# Debugger.net
KiCad netlist of a schematic drawn in Altium Designer
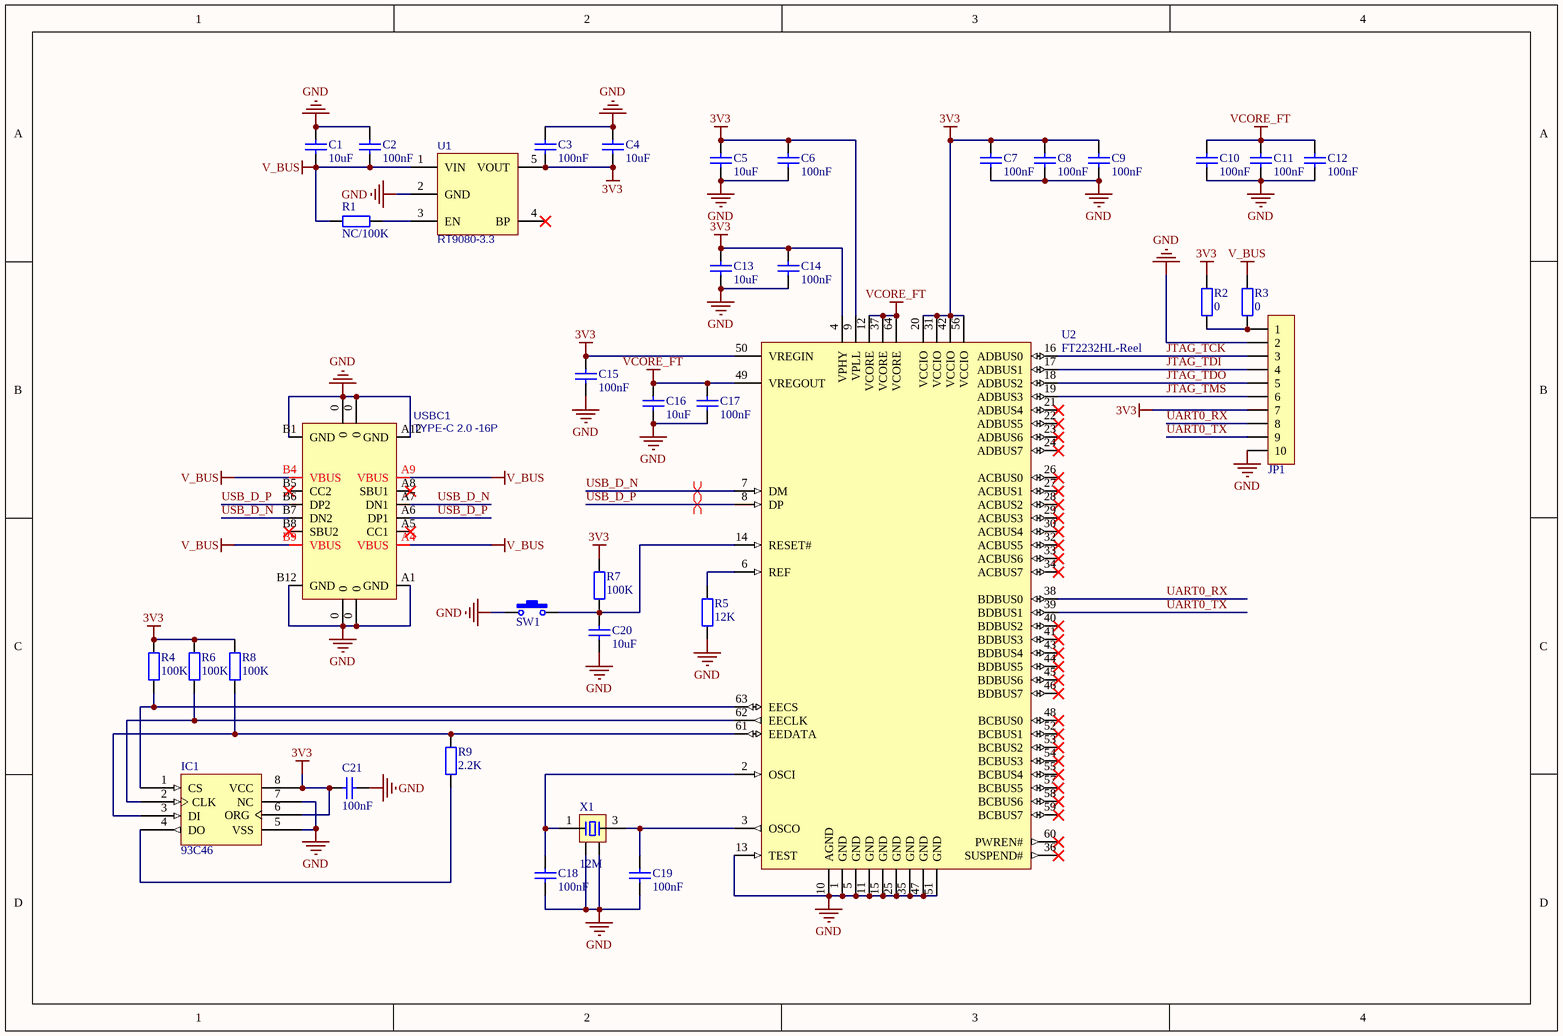
[diagram p0: Debugger.SchDoc]

(export (version "E")
  (design (tool "Eeschema 10.0.6"))
  (components
    (comp (ref "C1")
      (value "10uF")
      (footprint "C0603_L")
      (description "贴片电容/MLCC电容")
      (libsource (lib "0.1 - 电阻-电容-电感-晶振-晶体-磁珠-电位器-法拉电容-馈通电容") (part "C"))
    )
    (comp (ref "C2")
      (value "100nF")
      (footprint "C0603_L")
      (description "贴片电容/MLCC电容")
      (libsource (lib "0.1 - 电阻-电容-电感-晶振-晶体-磁珠-电位器-法拉电容-馈通电容") (part "C"))
    )
    (comp (ref "C3")
      (value "100nF")
      (footprint "C0603_L")
      (description "贴片电容/MLCC电容")
      (libsource (lib "0.1 - 电阻-电容-电感-晶振-晶体-磁珠-电位器-法拉电容-馈通电容") (part "C"))
    )
    (comp (ref "C4")
      (value "10uF")
      (footprint "C0603_L")
      (description "贴片电容/MLCC电容")
      (libsource (lib "0.1 - 电阻-电容-电感-晶振-晶体-磁珠-电位器-法拉电容-馈通电容") (part "C"))
    )
    (comp (ref "C5")
      (value "10uF")
      (footprint "C0603_L")
      (description "贴片电容/MLCC电容")
      (libsource (lib "0.1 - 电阻-电容-电感-晶振-晶体-磁珠-电位器-法拉电容-馈通电容") (part "C"))
    )
    (comp (ref "C6")
      (value "100nF")
      (footprint "C0603_L")
      (description "贴片电容/MLCC电容")
      (libsource (lib "0.1 - 电阻-电容-电感-晶振-晶体-磁珠-电位器-法拉电容-馈通电容") (part "C"))
    )
    (comp (ref "C7")
      (value "100nF")
      (footprint "C0603_L")
      (description "贴片电容/MLCC电容")
      (libsource (lib "0.1 - 电阻-电容-电感-晶振-晶体-磁珠-电位器-法拉电容-馈通电容") (part "C"))
    )
    (comp (ref "C8")
      (value "100nF")
      (footprint "C0603_L")
      (description "贴片电容/MLCC电容")
      (libsource (lib "0.1 - 电阻-电容-电感-晶振-晶体-磁珠-电位器-法拉电容-馈通电容") (part "C"))
    )
    (comp (ref "C9")
      (value "100nF")
      (footprint "C0603_L")
      (description "贴片电容/MLCC电容")
      (libsource (lib "0.1 - 电阻-电容-电感-晶振-晶体-磁珠-电位器-法拉电容-馈通电容") (part "C"))
    )
    (comp (ref "C10")
      (value "100nF")
      (footprint "C0603_L")
      (description "贴片电容/MLCC电容")
      (libsource (lib "0.1 - 电阻-电容-电感-晶振-晶体-磁珠-电位器-法拉电容-馈通电容") (part "C"))
    )
    (comp (ref "C11")
      (value "100nF")
      (footprint "C0603_L")
      (description "贴片电容/MLCC电容")
      (libsource (lib "0.1 - 电阻-电容-电感-晶振-晶体-磁珠-电位器-法拉电容-馈通电容") (part "C"))
    )
    (comp (ref "C12")
      (value "100nF")
      (footprint "C0603_L")
      (description "贴片电容/MLCC电容")
      (libsource (lib "0.1 - 电阻-电容-电感-晶振-晶体-磁珠-电位器-法拉电容-馈通电容") (part "C"))
    )
    (comp (ref "C13")
      (value "10uF")
      (footprint "C0603_L")
      (description "贴片电容/MLCC电容")
      (libsource (lib "0.1 - 电阻-电容-电感-晶振-晶体-磁珠-电位器-法拉电容-馈通电容") (part "C"))
    )
    (comp (ref "C14")
      (value "100nF")
      (footprint "C0603_L")
      (description "贴片电容/MLCC电容")
      (libsource (lib "0.1 - 电阻-电容-电感-晶振-晶体-磁珠-电位器-法拉电容-馈通电容") (part "C"))
    )
    (comp (ref "C15")
      (value "100nF")
      (footprint "C0603_L")
      (description "贴片电容/MLCC电容")
      (libsource (lib "0.1 - 电阻-电容-电感-晶振-晶体-磁珠-电位器-法拉电容-馈通电容") (part "C"))
    )
    (comp (ref "C16")
      (value "10uF")
      (footprint "C0603_L")
      (description "贴片电容/MLCC电容")
      (libsource (lib "0.1 - 电阻-电容-电感-晶振-晶体-磁珠-电位器-法拉电容-馈通电容") (part "C"))
    )
    (comp (ref "C17")
      (value "100nF")
      (footprint "C0603_L")
      (description "贴片电容/MLCC电容")
      (libsource (lib "0.1 - 电阻-电容-电感-晶振-晶体-磁珠-电位器-法拉电容-馈通电容") (part "C"))
    )
    (comp (ref "C18")
      (value "100nF")
      (footprint "C0603_L")
      (description "贴片电容/MLCC电容")
      (libsource (lib "0.1 - 电阻-电容-电感-晶振-晶体-磁珠-电位器-法拉电容-馈通电容") (part "C"))
    )
    (comp (ref "C19")
      (value "100nF")
      (footprint "C0603_L")
      (description "贴片电容/MLCC电容")
      (libsource (lib "0.1 - 电阻-电容-电感-晶振-晶体-磁珠-电位器-法拉电容-馈通电容") (part "C"))
    )
    (comp (ref "C20")
      (value "10uF")
      (footprint "C0603_L")
      (description "贴片电容/MLCC电容")
      (libsource (lib "0.1 - 电阻-电容-电感-晶振-晶体-磁珠-电位器-法拉电容-馈通电容") (part "C"))
    )
    (comp (ref "C21")
      (value "100nF")
      (footprint "C0603_L")
      (description "贴片电容/MLCC电容")
      (libsource (lib "0.1 - 电阻-电容-电感-晶振-晶体-磁珠-电位器-法拉电容-馈通电容") (part "C"))
    )
    (comp (ref "IC1")
      (value "93C46")
      (footprint "SOP8_L")
      (description "外置EEPROM")
      (libsource (lib "0.8 - 常见芯片") (part "93C46"))
    )
    (comp (ref "JP1")
      (value "HDR-1X10")
      (footprint "HDR2.54-LI-10P")
      (description "10P接插件")
      (libsource (lib "5.5 - 2.54mm连接器(KF2EDGK_XH2.54_2.54排针排母)") (part "Header 10"))
    )
    (comp (ref "R1")
      (value "NC/100K")
      (footprint "R0603_L")
      (description "贴片电阻")
      (libsource (lib "0.1 - 电阻-电容-电感-晶振-晶体-磁珠-电位器-法拉电容-馈通电容") (part "R"))
    )
    (comp (ref "R2")
      (value "0")
      (footprint "R0603_L")
      (description "贴片电阻")
      (libsource (lib "0.1 - 电阻-电容-电感-晶振-晶体-磁珠-电位器-法拉电容-馈通电容") (part "R"))
    )
    (comp (ref "R3")
      (value "0")
      (footprint "R0603_L")
      (description "贴片电阻")
      (libsource (lib "0.1 - 电阻-电容-电感-晶振-晶体-磁珠-电位器-法拉电容-馈通电容") (part "R"))
    )
    (comp (ref "R4")
      (value "100K")
      (footprint "R0603_L")
      (description "贴片电阻")
      (libsource (lib "0.1 - 电阻-电容-电感-晶振-晶体-磁珠-电位器-法拉电容-馈通电容") (part "R"))
    )
    (comp (ref "R5")
      (value "12K")
      (footprint "R0603_L")
      (description "贴片电阻")
      (libsource (lib "0.1 - 电阻-电容-电感-晶振-晶体-磁珠-电位器-法拉电容-馈通电容") (part "R"))
    )
    (comp (ref "R6")
      (value "100K")
      (footprint "R0603_L")
      (description "贴片电阻")
      (libsource (lib "0.1 - 电阻-电容-电感-晶振-晶体-磁珠-电位器-法拉电容-馈通电容") (part "R"))
    )
    (comp (ref "R7")
      (value "100K")
      (footprint "R0603_L")
      (description "贴片电阻")
      (libsource (lib "0.1 - 电阻-电容-电感-晶振-晶体-磁珠-电位器-法拉电容-馈通电容") (part "R"))
    )
    (comp (ref "R8")
      (value "100K")
      (footprint "R0603_L")
      (description "贴片电阻")
      (libsource (lib "0.1 - 电阻-电容-电感-晶振-晶体-磁珠-电位器-法拉电容-馈通电容") (part "R"))
    )
    (comp (ref "R9")
      (value "2.2K")
      (footprint "R0603_L")
      (description "贴片电阻")
      (libsource (lib "0.1 - 电阻-电容-电感-晶振-晶体-磁珠-电位器-法拉电容-馈通电容") (part "R"))
    )
    (comp (ref "SW1")
      (value "3x6x5")
      (footprint "SW SMD-3*6*2.5")
      (description "3x6轻触开关")
      (libsource (lib "0.5 - 按键_开关_蜂鸣器_保险丝_电池_测试点_Mark点_铜柱") (part "SW 3x6"))
    )
    (comp (ref "U1")
      (value "RT9080-3.3")
      (footprint "SOT-23-5")
      (description "LDO 1.8V/0.3A")
      (libsource (lib "0.7 - 电源类芯片") (part "RT9193-18GB"))
    )
    (comp (ref "U2")
      (value "FT2232HL-Reel")
      (footprint "LQFP-64_N")
      (description "Dual High Speed USB To Multipurpose UART/FIFO IC, 64-pin LQFP, Tape and Reel")
      (fields (field (name "MANUFACTURER") "FTDI"))
      (libsource (lib "Altium Content Vault") (part "COM-UART-FT2232H-LQFP64"))
    )
    (comp (ref "USBC1")
      (value "TYPE-C 2.0 -16P")
      (footprint "USB-C-SMD_16P")
      (description "USB2.0_Type-C_16Pin母座")
      (libsource (lib "0.6 - 电源_RJ45以太网_音频_SD-TF_SIM_ USB Type-C_HDMI插座") (part "USB2.0_Type-C_16Pin"))
    )
    (comp (ref "X1")
      (value "12M")
      (footprint "XTAL-2025-4P")
      (description "4脚无源晶振(谐振器）")
      (libsource (lib "0.1 - 电阻-电容-电感-晶振-晶体-磁珠-电位器-法拉电容-馈通电容") (part "XTAL-4P"))
    )
  )
  (nets
    (net (code "1") (name "/JTAG_TCK") (class "Default")
      (node (ref "JP1") (pin "3") (pinfunction "3_3") (pintype "passive"))
      (node (ref "U2") (pin "16") (pinfunction "ADBUS0_16") (pintype "bidirectional"))
    )
    (net (code "2") (name "/JTAG_TDI") (class "Default")
      (node (ref "JP1") (pin "4") (pinfunction "4_4") (pintype "passive"))
      (node (ref "U2") (pin "17") (pinfunction "ADBUS1_17") (pintype "bidirectional"))
    )
    (net (code "3") (name "/JTAG_TDO") (class "Default")
      (node (ref "JP1") (pin "5") (pinfunction "5_5") (pintype "passive"))
      (node (ref "U2") (pin "18") (pinfunction "ADBUS2_18") (pintype "bidirectional"))
    )
    (net (code "4") (name "/JTAG_TMS") (class "Default")
      (node (ref "JP1") (pin "6") (pinfunction "6_6") (pintype "passive"))
      (node (ref "U2") (pin "19") (pinfunction "ADBUS3_19") (pintype "bidirectional"))
    )
    (net (code "5") (name "/UART0_RX") (class "Default")
      (node (ref "JP1") (pin "8") (pinfunction "8_8") (pintype "passive"))
      (node (ref "U2") (pin "38") (pinfunction "BDBUS0_38") (pintype "bidirectional"))
    )
    (net (code "6") (name "/UART0_TX") (class "Default")
      (node (ref "JP1") (pin "9") (pinfunction "9_9") (pintype "passive"))
      (node (ref "U2") (pin "39") (pinfunction "BDBUS1_39") (pintype "bidirectional"))
    )
    (net (code "7") (name "/USB_D_N") (class "Default")
      (node (ref "U2") (pin "7") (pinfunction "DM_7") (pintype "input"))
      (node (ref "USBC1") (pin "A7") (pinfunction "DN1_A7") (pintype "passive"))
      (node (ref "USBC1") (pin "B7") (pinfunction "DN2_B7") (pintype "passive"))
    )
    (net (code "8") (name "/USB_D_P") (class "Default")
      (node (ref "U2") (pin "8") (pinfunction "DP_8") (pintype "input"))
      (node (ref "USBC1") (pin "A6") (pinfunction "DP1_A6") (pintype "passive"))
      (node (ref "USBC1") (pin "B6") (pinfunction "DP2_B6") (pintype "passive"))
    )
    (net (code "9") (name "3V3") (class "Default")
      (node (ref "C13") (pin "2") (pinfunction "2_2") (pintype "passive"))
      (node (ref "C14") (pin "2") (pinfunction "2_2") (pintype "passive"))
      (node (ref "C15") (pin "2") (pinfunction "2_2") (pintype "passive"))
      (node (ref "C21") (pin "1") (pinfunction "1_1") (pintype "passive"))
      (node (ref "C3") (pin "1") (pinfunction "1_1") (pintype "passive"))
      (node (ref "C4") (pin "1") (pinfunction "1_1") (pintype "passive"))
      (node (ref "C5") (pin "2") (pinfunction "2_2") (pintype "passive"))
      (node (ref "C6") (pin "2") (pinfunction "2_2") (pintype "passive"))
      (node (ref "C7") (pin "2") (pinfunction "2_2") (pintype "passive"))
      (node (ref "C8") (pin "2") (pinfunction "2_2") (pintype "passive"))
      (node (ref "C9") (pin "2") (pinfunction "2_2") (pintype "passive"))
      (node (ref "IC1") (pin "6") (pinfunction "ORG_6") (pintype "passive"))
      (node (ref "IC1") (pin "8") (pinfunction "VCC_8") (pintype "power_in"))
      (node (ref "JP1") (pin "7") (pinfunction "7_7") (pintype "passive"))
      (node (ref "R2") (pin "2") (pinfunction "2_2") (pintype "passive"))
      (node (ref "R4") (pin "2") (pinfunction "2_2") (pintype "passive"))
      (node (ref "R6") (pin "2") (pinfunction "2_2") (pintype "passive"))
      (node (ref "R7") (pin "2") (pinfunction "2_2") (pintype "passive"))
      (node (ref "R8") (pin "2") (pinfunction "2_2") (pintype "passive"))
      (node (ref "U1") (pin "5") (pinfunction "VOUT_5") (pintype "passive"))
      (node (ref "U2") (pin "20") (pinfunction "VCCIO_20") (pintype "power_in"))
      (node (ref "U2") (pin "31") (pinfunction "VCCIO_31") (pintype "power_in"))
      (node (ref "U2") (pin "4") (pinfunction "VPHY_4") (pintype "power_in"))
      (node (ref "U2") (pin "42") (pinfunction "VCCIO_42") (pintype "power_in"))
      (node (ref "U2") (pin "50") (pinfunction "VREGIN_50") (pintype "power_in"))
      (node (ref "U2") (pin "56") (pinfunction "VCCIO_56") (pintype "power_in"))
      (node (ref "U2") (pin "9") (pinfunction "VPLL_9") (pintype "power_in"))
    )
    (net (code "10") (name "GND") (class "Default")
      (node (ref "C1") (pin "2") (pinfunction "2_2") (pintype "passive"))
      (node (ref "C10") (pin "1") (pinfunction "1_1") (pintype "passive"))
      (node (ref "C11") (pin "1") (pinfunction "1_1") (pintype "passive"))
      (node (ref "C12") (pin "1") (pinfunction "1_1") (pintype "passive"))
      (node (ref "C13") (pin "1") (pinfunction "1_1") (pintype "passive"))
      (node (ref "C14") (pin "1") (pinfunction "1_1") (pintype "passive"))
      (node (ref "C15") (pin "1") (pinfunction "1_1") (pintype "passive"))
      (node (ref "C16") (pin "1") (pinfunction "1_1") (pintype "passive"))
      (node (ref "C17") (pin "1") (pinfunction "1_1") (pintype "passive"))
      (node (ref "C18") (pin "1") (pinfunction "1_1") (pintype "passive"))
      (node (ref "C19") (pin "1") (pinfunction "1_1") (pintype "passive"))
      (node (ref "C2") (pin "2") (pinfunction "2_2") (pintype "passive"))
      (node (ref "C20") (pin "1") (pinfunction "1_1") (pintype "passive"))
      (node (ref "C21") (pin "2") (pinfunction "2_2") (pintype "passive"))
      (node (ref "C3") (pin "2") (pinfunction "2_2") (pintype "passive"))
      (node (ref "C4") (pin "2") (pinfunction "2_2") (pintype "passive"))
      (node (ref "C5") (pin "1") (pinfunction "1_1") (pintype "passive"))
      (node (ref "C6") (pin "1") (pinfunction "1_1") (pintype "passive"))
      (node (ref "C7") (pin "1") (pinfunction "1_1") (pintype "passive"))
      (node (ref "C8") (pin "1") (pinfunction "1_1") (pintype "passive"))
      (node (ref "C9") (pin "1") (pinfunction "1_1") (pintype "passive"))
      (node (ref "IC1") (pin "5") (pinfunction "VSS_5") (pintype "passive"))
      (node (ref "IC1") (pin "7") (pinfunction "NC_7") (pintype "passive"))
      (node (ref "JP1") (pin "10") (pinfunction "10_10") (pintype "passive"))
      (node (ref "JP1") (pin "2") (pinfunction "2_2") (pintype "passive"))
      (node (ref "R5") (pin "1") (pinfunction "1_1") (pintype "passive"))
      (node (ref "SW1") (pin "1") (pinfunction "1_1") (pintype "passive"))
      (node (ref "U1") (pin "2") (pinfunction "GND_2") (pintype "passive"))
      (node (ref "U2") (pin "1") (pinfunction "GND_1") (pintype "power_in"))
      (node (ref "U2") (pin "10") (pinfunction "AGND_10") (pintype "power_in"))
      (node (ref "U2") (pin "11") (pinfunction "GND_11") (pintype "power_in"))
      (node (ref "U2") (pin "13") (pinfunction "TEST_13") (pintype "input"))
      (node (ref "U2") (pin "15") (pinfunction "GND_15") (pintype "power_in"))
      (node (ref "U2") (pin "25") (pinfunction "GND_25") (pintype "power_in"))
      (node (ref "U2") (pin "35") (pinfunction "GND_35") (pintype "power_in"))
      (node (ref "U2") (pin "47") (pinfunction "GND_47") (pintype "power_in"))
      (node (ref "U2") (pin "5") (pinfunction "GND_5") (pintype "power_in"))
      (node (ref "U2") (pin "51") (pinfunction "GND_51") (pintype "power_in"))
      (node (ref "USBC1") (pin "0") (pinfunction "0_0") (pintype "passive"))
      (node (ref "USBC1") (pin "A1") (pinfunction "GND_A1") (pintype "passive"))
      (node (ref "USBC1") (pin "A12") (pinfunction "GND_A12") (pintype "passive"))
      (node (ref "USBC1") (pin "B1") (pinfunction "GND_B1") (pintype "passive"))
      (node (ref "USBC1") (pin "B12") (pinfunction "GND_B12") (pintype "passive"))
      (node (ref "X1") (pin "2") (pinfunction "2_2") (pintype "passive"))
      (node (ref "X1") (pin "4") (pinfunction "4_4") (pintype "passive"))
    )
    (net (code "11") (name "Net-(IC1-CLK)") (class "Default")
      (node (ref "IC1") (pin "2") (pinfunction "CLK_2") (pintype "input"))
      (node (ref "R6") (pin "1") (pinfunction "1_1") (pintype "passive"))
      (node (ref "U2") (pin "62") (pinfunction "EECLK_62") (pintype "output"))
    )
    (net (code "12") (name "Net-(IC1-CS)") (class "Default")
      (node (ref "IC1") (pin "1") (pinfunction "CS_1") (pintype "input"))
      (node (ref "R4") (pin "1") (pinfunction "1_1") (pintype "passive"))
      (node (ref "U2") (pin "63") (pinfunction "EECS_63") (pintype "bidirectional"))
    )
    (net (code "13") (name "Net-(IC1-DI)") (class "Default")
      (node (ref "IC1") (pin "3") (pinfunction "DI_3") (pintype "input"))
      (node (ref "R8") (pin "1") (pinfunction "1_1") (pintype "passive"))
      (node (ref "R9") (pin "1") (pinfunction "1_1") (pintype "passive"))
      (node (ref "U2") (pin "61") (pinfunction "EEDATA_61") (pintype "bidirectional"))
    )
    (net (code "14") (name "Net-(IC1-DO)") (class "Default")
      (node (ref "IC1") (pin "4") (pinfunction "DO_4") (pintype "output"))
      (node (ref "R9") (pin "2") (pinfunction "2_2") (pintype "passive"))
    )
    (net (code "15") (name "Net-(JP1-Pad1)") (class "Default")
      (node (ref "JP1") (pin "1") (pinfunction "1_1") (pintype "passive"))
      (node (ref "R2") (pin "1") (pinfunction "1_1") (pintype "passive"))
      (node (ref "R3") (pin "1") (pinfunction "1_1") (pintype "passive"))
    )
    (net (code "16") (name "Net-(U1-EN)") (class "Default")
      (node (ref "R1") (pin "2") (pinfunction "2_2") (pintype "passive"))
      (node (ref "U1") (pin "3") (pinfunction "EN_3") (pintype "passive"))
    )
    (net (code "17") (name "Net-(U2-OSCI)") (class "Default")
      (node (ref "C18") (pin "2") (pinfunction "2_2") (pintype "passive"))
      (node (ref "U2") (pin "2") (pinfunction "OSCI_2") (pintype "input"))
      (node (ref "X1") (pin "1") (pinfunction "1_1") (pintype "passive"))
    )
    (net (code "18") (name "Net-(U2-OSCO)") (class "Default")
      (node (ref "C19") (pin "2") (pinfunction "2_2") (pintype "passive"))
      (node (ref "U2") (pin "3") (pinfunction "OSCO_3") (pintype "output"))
      (node (ref "X1") (pin "3") (pinfunction "3_3") (pintype "passive"))
    )
    (net (code "19") (name "Net-(U2-REF)") (class "Default")
      (node (ref "R5") (pin "2") (pinfunction "2_2") (pintype "passive"))
      (node (ref "U2") (pin "6") (pinfunction "REF_6") (pintype "input"))
    )
    (net (code "20") (name "Net-(U2-RESET#)") (class "Default")
      (node (ref "C20") (pin "2") (pinfunction "2_2") (pintype "passive"))
      (node (ref "R7") (pin "1") (pinfunction "1_1") (pintype "passive"))
      (node (ref "SW1") (pin "2") (pinfunction "2_2") (pintype "passive"))
      (node (ref "U2") (pin "14") (pinfunction "RESET#_14") (pintype "input"))
    )
    (net (code "21") (name "VCORE_FT") (class "Default")
      (node (ref "C10") (pin "2") (pinfunction "2_2") (pintype "passive"))
      (node (ref "C11") (pin "2") (pinfunction "2_2") (pintype "passive"))
      (node (ref "C12") (pin "2") (pinfunction "2_2") (pintype "passive"))
      (node (ref "C16") (pin "2") (pinfunction "2_2") (pintype "passive"))
      (node (ref "C17") (pin "2") (pinfunction "2_2") (pintype "passive"))
      (node (ref "U2") (pin "12") (pinfunction "VCORE_12") (pintype "power_in"))
      (node (ref "U2") (pin "37") (pinfunction "VCORE_37") (pintype "power_in"))
      (node (ref "U2") (pin "49") (pinfunction "VREGOUT_49") (pintype "power_in"))
      (node (ref "U2") (pin "64") (pinfunction "VCORE_64") (pintype "power_in"))
    )
    (net (code "22") (name "V_BUS") (class "Default")
      (node (ref "C1") (pin "1") (pinfunction "1_1") (pintype "passive"))
      (node (ref "C2") (pin "1") (pinfunction "1_1") (pintype "passive"))
      (node (ref "R1") (pin "1") (pinfunction "1_1") (pintype "passive"))
      (node (ref "R3") (pin "2") (pinfunction "2_2") (pintype "passive"))
      (node (ref "U1") (pin "1") (pinfunction "VIN_1") (pintype "passive"))
      (node (ref "USBC1") (pin "A4") (pinfunction "VBUS_A4") (pintype "passive"))
      (node (ref "USBC1") (pin "A9") (pinfunction "VBUS_A9") (pintype "passive"))
      (node (ref "USBC1") (pin "B4") (pinfunction "VBUS_B4") (pintype "passive"))
      (node (ref "USBC1") (pin "B9") (pinfunction "VBUS_B9") (pintype "passive"))
    )
    (net (code "23") (name "unconnected-(U1-BP-Pad4)") (class "Default")
      (node (ref "U1") (pin "4") (pinfunction "BP_4") (pintype "passive+no_connect"))
    )
    (net (code "24") (name "unconnected-(U2-ACBUS0-Pad26)") (class "Default")
      (node (ref "U2") (pin "26") (pinfunction "ACBUS0_26") (pintype "bidirectional+no_connect"))
    )
    (net (code "25") (name "unconnected-(U2-ACBUS1-Pad27)") (class "Default")
      (node (ref "U2") (pin "27") (pinfunction "ACBUS1_27") (pintype "bidirectional+no_connect"))
    )
    (net (code "26") (name "unconnected-(U2-ACBUS2-Pad28)") (class "Default")
      (node (ref "U2") (pin "28") (pinfunction "ACBUS2_28") (pintype "bidirectional+no_connect"))
    )
    (net (code "27") (name "unconnected-(U2-ACBUS3-Pad29)") (class "Default")
      (node (ref "U2") (pin "29") (pinfunction "ACBUS3_29") (pintype "bidirectional+no_connect"))
    )
    (net (code "28") (name "unconnected-(U2-ACBUS4-Pad30)") (class "Default")
      (node (ref "U2") (pin "30") (pinfunction "ACBUS4_30") (pintype "bidirectional+no_connect"))
    )
    (net (code "29") (name "unconnected-(U2-ACBUS5-Pad32)") (class "Default")
      (node (ref "U2") (pin "32") (pinfunction "ACBUS5_32") (pintype "bidirectional+no_connect"))
    )
    (net (code "30") (name "unconnected-(U2-ACBUS6-Pad33)") (class "Default")
      (node (ref "U2") (pin "33") (pinfunction "ACBUS6_33") (pintype "bidirectional+no_connect"))
    )
    (net (code "31") (name "unconnected-(U2-ACBUS7-Pad34)") (class "Default")
      (node (ref "U2") (pin "34") (pinfunction "ACBUS7_34") (pintype "bidirectional+no_connect"))
    )
    (net (code "32") (name "unconnected-(U2-ADBUS4-Pad21)") (class "Default")
      (node (ref "U2") (pin "21") (pinfunction "ADBUS4_21") (pintype "bidirectional+no_connect"))
    )
    (net (code "33") (name "unconnected-(U2-ADBUS5-Pad22)") (class "Default")
      (node (ref "U2") (pin "22") (pinfunction "ADBUS5_22") (pintype "bidirectional+no_connect"))
    )
    (net (code "34") (name "unconnected-(U2-ADBUS6-Pad23)") (class "Default")
      (node (ref "U2") (pin "23") (pinfunction "ADBUS6_23") (pintype "bidirectional+no_connect"))
    )
    (net (code "35") (name "unconnected-(U2-ADBUS7-Pad24)") (class "Default")
      (node (ref "U2") (pin "24") (pinfunction "ADBUS7_24") (pintype "bidirectional+no_connect"))
    )
    (net (code "36") (name "unconnected-(U2-BCBUS0-Pad48)") (class "Default")
      (node (ref "U2") (pin "48") (pinfunction "BCBUS0_48") (pintype "bidirectional+no_connect"))
    )
    (net (code "37") (name "unconnected-(U2-BCBUS1-Pad52)") (class "Default")
      (node (ref "U2") (pin "52") (pinfunction "BCBUS1_52") (pintype "bidirectional+no_connect"))
    )
    (net (code "38") (name "unconnected-(U2-BCBUS2-Pad53)") (class "Default")
      (node (ref "U2") (pin "53") (pinfunction "BCBUS2_53") (pintype "bidirectional+no_connect"))
    )
    (net (code "39") (name "unconnected-(U2-BCBUS3-Pad54)") (class "Default")
      (node (ref "U2") (pin "54") (pinfunction "BCBUS3_54") (pintype "bidirectional+no_connect"))
    )
    (net (code "40") (name "unconnected-(U2-BCBUS4-Pad55)") (class "Default")
      (node (ref "U2") (pin "55") (pinfunction "BCBUS4_55") (pintype "bidirectional+no_connect"))
    )
    (net (code "41") (name "unconnected-(U2-BCBUS5-Pad57)") (class "Default")
      (node (ref "U2") (pin "57") (pinfunction "BCBUS5_57") (pintype "bidirectional+no_connect"))
    )
    (net (code "42") (name "unconnected-(U2-BCBUS6-Pad58)") (class "Default")
      (node (ref "U2") (pin "58") (pinfunction "BCBUS6_58") (pintype "bidirectional+no_connect"))
    )
    (net (code "43") (name "unconnected-(U2-BCBUS7-Pad59)") (class "Default")
      (node (ref "U2") (pin "59") (pinfunction "BCBUS7_59") (pintype "bidirectional+no_connect"))
    )
    (net (code "44") (name "unconnected-(U2-BDBUS2-Pad40)") (class "Default")
      (node (ref "U2") (pin "40") (pinfunction "BDBUS2_40") (pintype "bidirectional+no_connect"))
    )
    (net (code "45") (name "unconnected-(U2-BDBUS3-Pad41)") (class "Default")
      (node (ref "U2") (pin "41") (pinfunction "BDBUS3_41") (pintype "bidirectional+no_connect"))
    )
    (net (code "46") (name "unconnected-(U2-BDBUS4-Pad43)") (class "Default")
      (node (ref "U2") (pin "43") (pinfunction "BDBUS4_43") (pintype "bidirectional+no_connect"))
    )
    (net (code "47") (name "unconnected-(U2-BDBUS5-Pad44)") (class "Default")
      (node (ref "U2") (pin "44") (pinfunction "BDBUS5_44") (pintype "bidirectional+no_connect"))
    )
    (net (code "48") (name "unconnected-(U2-BDBUS6-Pad45)") (class "Default")
      (node (ref "U2") (pin "45") (pinfunction "BDBUS6_45") (pintype "bidirectional+no_connect"))
    )
    (net (code "49") (name "unconnected-(U2-BDBUS7-Pad46)") (class "Default")
      (node (ref "U2") (pin "46") (pinfunction "BDBUS7_46") (pintype "bidirectional+no_connect"))
    )
    (net (code "50") (name "unconnected-(U2-PWREN#-Pad60)") (class "Default")
      (node (ref "U2") (pin "60") (pinfunction "PWREN#_60") (pintype "output+no_connect"))
    )
    (net (code "51") (name "unconnected-(U2-SUSPEND#-Pad36)") (class "Default")
      (node (ref "U2") (pin "36") (pinfunction "SUSPEND#_36") (pintype "output+no_connect"))
    )
    (net (code "52") (name "unconnected-(USBC1-CC1-PadA5)") (class "Default")
      (node (ref "USBC1") (pin "A5") (pinfunction "CC1_A5") (pintype "passive+no_connect"))
    )
    (net (code "53") (name "unconnected-(USBC1-CC2-PadB5)") (class "Default")
      (node (ref "USBC1") (pin "B5") (pinfunction "CC2_B5") (pintype "passive+no_connect"))
    )
    (net (code "54") (name "unconnected-(USBC1-SBU1-PadA8)") (class "Default")
      (node (ref "USBC1") (pin "A8") (pinfunction "SBU1_A8") (pintype "passive+no_connect"))
    )
    (net (code "55") (name "unconnected-(USBC1-SBU2-PadB8)") (class "Default")
      (node (ref "USBC1") (pin "B8") (pinfunction "SBU2_B8") (pintype "passive+no_connect"))
    )
  )
)
